# HP85disk_03.net
KiCad netlist of a schematic drawn in EAGLE
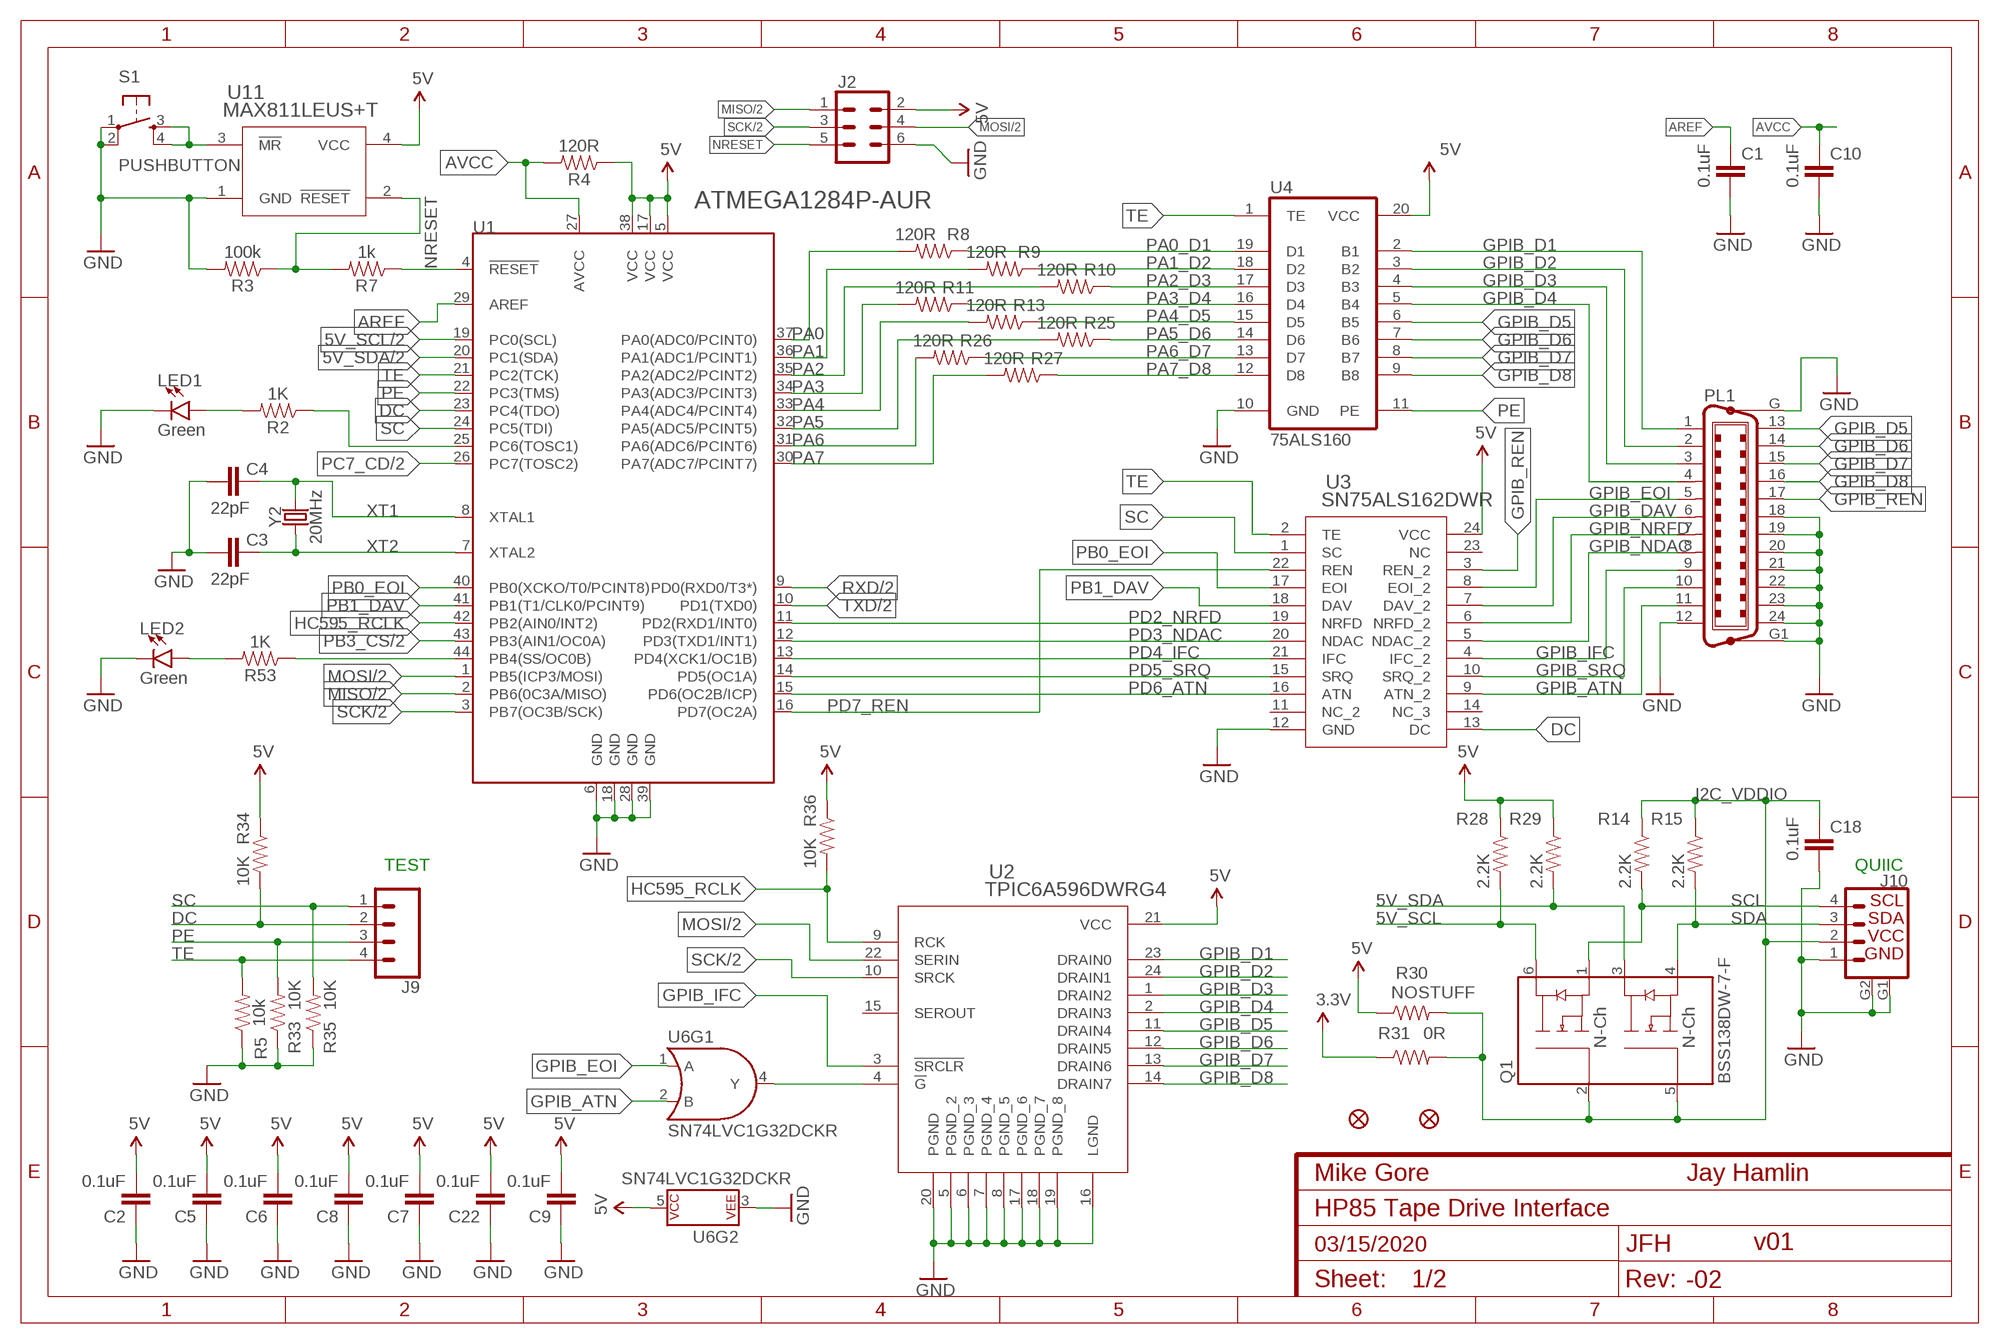
[diagram p0: schematic, sheet 1]
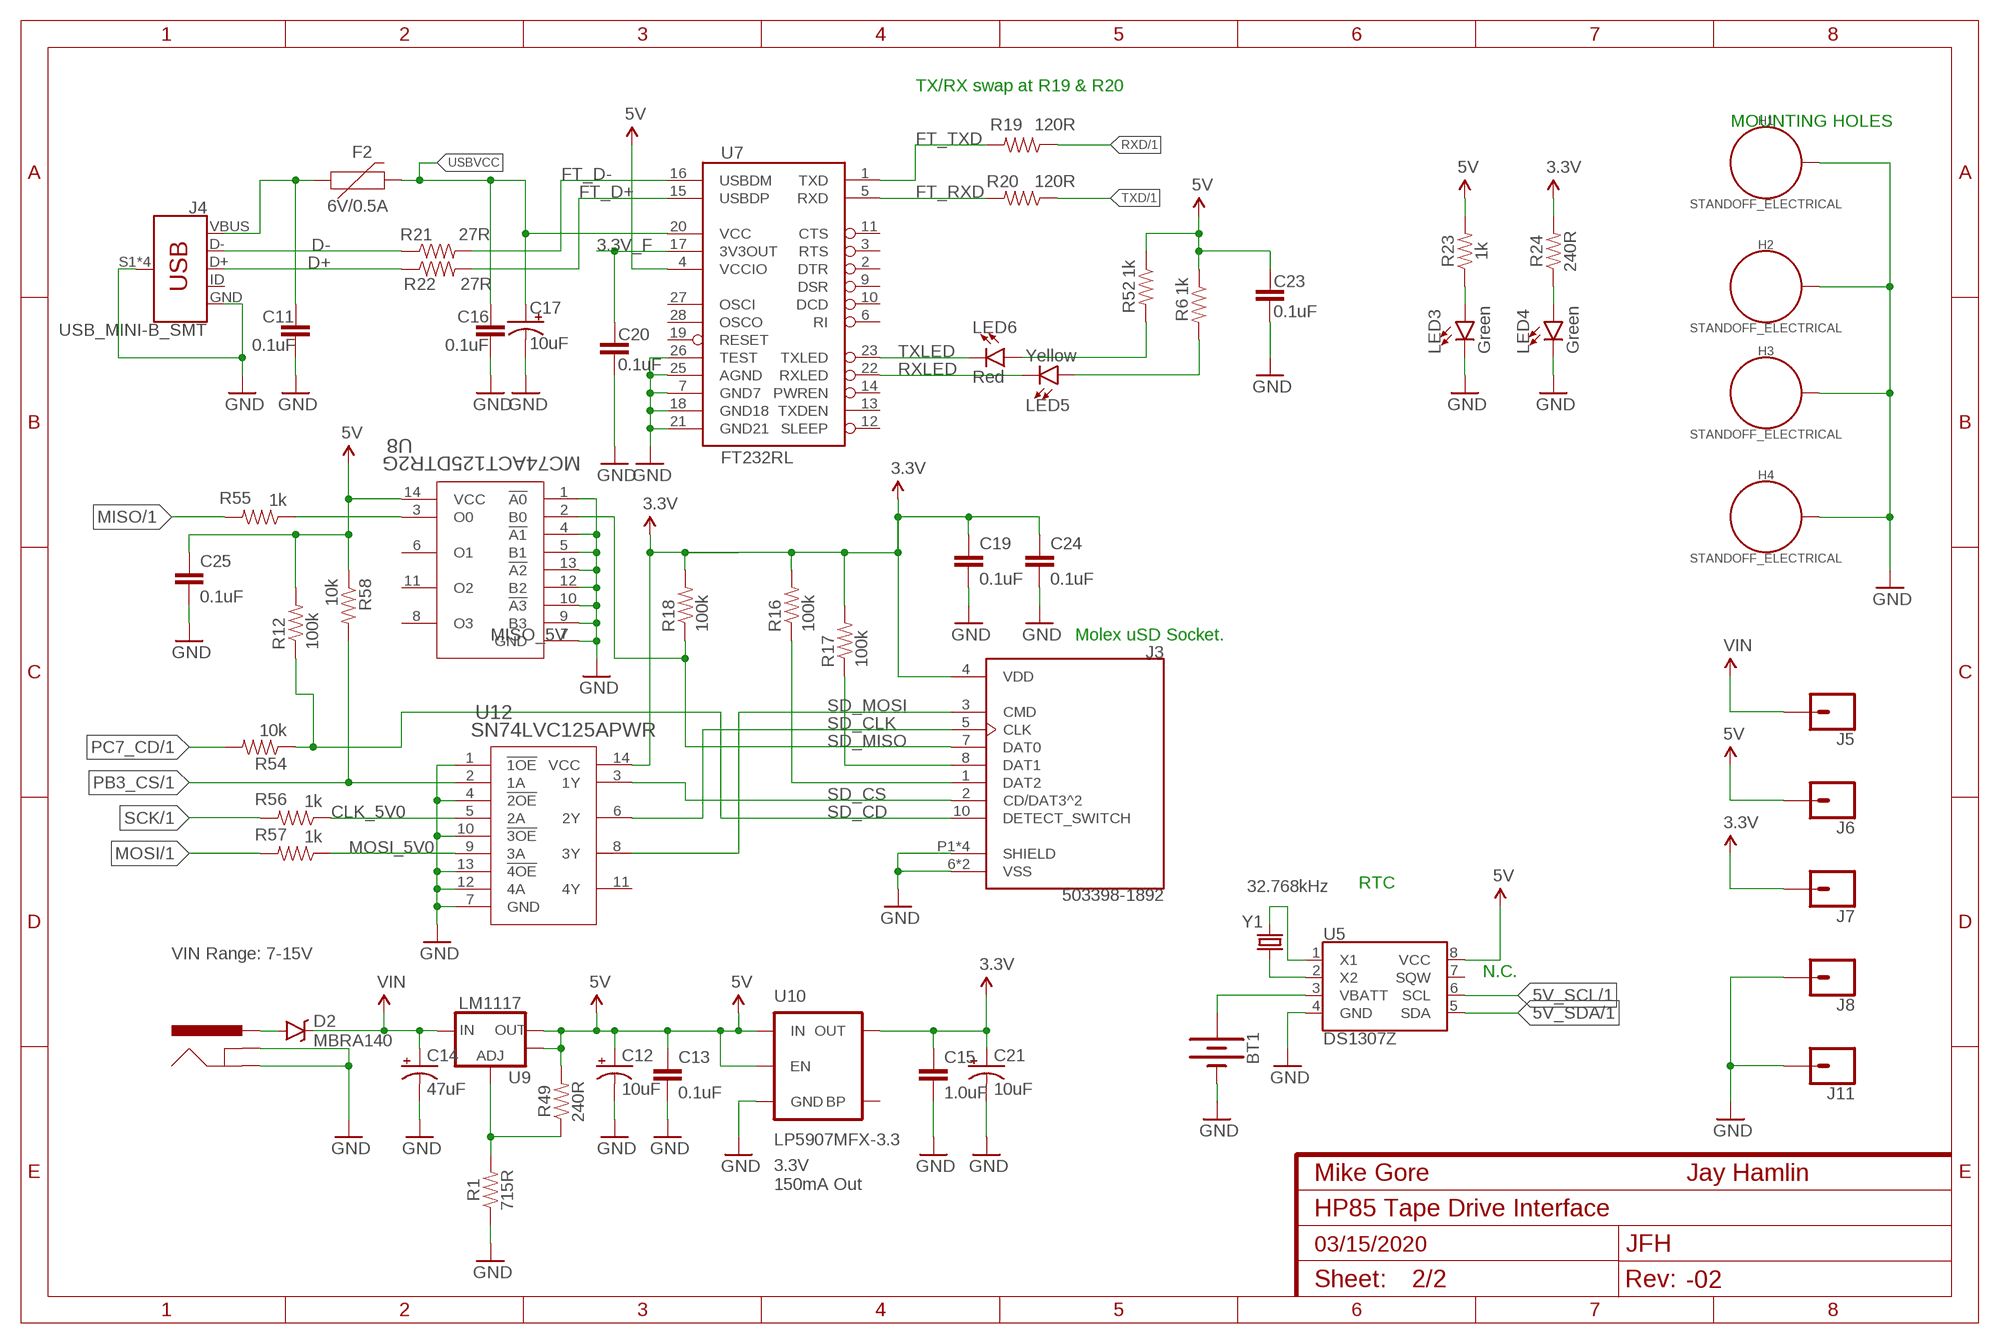
[diagram p1: schematic, sheet 2]

(export (version "E")
  (design (tool "Eeschema 10.0.6"))
  (components
    (comp (ref "C1")
      (value "0.1uF")
      (footprint "eagle-import:0603")
      (libsource (lib "eagle-import") (part "0.1UF-0603-25V-(+80/-20%)"))
    )
    (comp (ref "C2")
      (value "0.1uF")
      (footprint "eagle-import:0603")
      (fields (field (name "SPICEPREFIX") "C"))
      (libsource (lib "eagle-import") (part "0.1UF-0603-25V-(+80/-20%)"))
    )
    (comp (ref "C3")
      (value "22pF")
      (footprint "eagle-import:0603")
      (libsource (lib "eagle-import") (part "0.1UF-0603-25V-(+80/-20%)"))
    )
    (comp (ref "C4")
      (value "22pF")
      (footprint "eagle-import:0603")
      (libsource (lib "eagle-import") (part "0.1UF-0603-25V-(+80/-20%)"))
    )
    (comp (ref "C5")
      (value "0.1uF")
      (footprint "eagle-import:0603")
      (fields (field (name "SPICEPREFIX") "C"))
      (libsource (lib "eagle-import") (part "0.1UF-0603-25V-(+80/-20%)"))
    )
    (comp (ref "C6")
      (value "0.1uF")
      (footprint "eagle-import:0603")
      (fields (field (name "SPICEPREFIX") "C"))
      (libsource (lib "eagle-import") (part "0.1UF-0603-25V-(+80/-20%)"))
    )
    (comp (ref "C7")
      (value "0.1uF")
      (footprint "eagle-import:0603")
      (fields (field (name "SPICEPREFIX") "C"))
      (libsource (lib "eagle-import") (part "0.1UF-0603-25V-(+80/-20%)"))
    )
    (comp (ref "C8")
      (value "0.1uF")
      (footprint "eagle-import:0603")
      (fields (field (name "SPICEPREFIX") "C"))
      (libsource (lib "eagle-import") (part "0.1UF-0603-25V-(+80/-20%)"))
    )
    (comp (ref "C9")
      (value "0.1uF")
      (footprint "eagle-import:0603")
      (libsource (lib "eagle-import") (part "0.1UF-0603-25V-(+80/-20%)"))
    )
    (comp (ref "C10")
      (value "0.1uF")
      (footprint "eagle-import:0603")
      (libsource (lib "eagle-import") (part "0.1UF-0603-25V-(+80/-20%)"))
    )
    (comp (ref "C18")
      (value "0.1uF")
      (footprint "eagle-import:0603")
      (libsource (lib "eagle-import") (part "0.1UF-0603-25V-(+80/-20%)"))
    )
    (comp (ref "C22")
      (value "0.1uF")
      (footprint "eagle-import:0603")
      (libsource (lib "eagle-import") (part "0.1UF-0603-25V-(+80/-20%)"))
    )
    (comp (ref "J2")
      (value "CONN_03X2_BIGPADSFEMALE_SMD")
      (footprint "eagle-import:2X3_SMD")
      (libsource (lib "eagle-import") (part "CONN_03X2_BIGPADSFEMALE_SMD"))
    )
    (comp (ref "J9")
      (value "CONN_041.27MM")
      (footprint "eagle-import:1X04_1.27MM")
      (libsource (lib "eagle-import") (part "CONN_041.27MM"))
    )
    (comp (ref "J10")
      (value "QWIIC_CONNECTORJS-1MM")
      (footprint "eagle-import:QUIIC_1X04_1MM_RA")
      (libsource (lib "eagle-import") (part "QWIIC_CONNECTORJS-1MM"))
    )
    (comp (ref "JP8")
      (value "FIDUCIAL1X2")
      (footprint "eagle-import:FIDUCIAL-1X2")
      (libsource (lib "eagle-import") (part "FIDUCIAL1X2"))
    )
    (comp (ref "JP9")
      (value "FIDUCIAL1X2")
      (footprint "eagle-import:FIDUCIAL-1X2")
      (libsource (lib "eagle-import") (part "FIDUCIAL1X2"))
    )
    (comp (ref "LED1")
      (value "Green")
      (footprint "eagle-import:LED-1206")
      (libsource (lib "eagle-import") (part "LED1206"))
    )
    (comp (ref "LED2")
      (value "Green")
      (footprint "eagle-import:LED-1206")
      (libsource (lib "eagle-import") (part "LED1206"))
    )
    (comp (ref "PL1")
      (value "C24HP")
      (footprint "eagle-import:24HP")
      (libsource (lib "eagle-import") (part "C24HP"))
    )
    (comp (ref "Q1")
      (value "BSS138DW-7-F")
      (footprint "eagle-import:SOT-363")
      (libsource (lib "eagle-import") (part "BSS138DW-7-F"))
    )
    (comp (ref "R2")
      (value "1K")
      (footprint "eagle-import:0603")
      (libsource (lib "eagle-import") (part "4.7KOHM-0603-1/10W-1%"))
    )
    (comp (ref "R3")
      (value "100k")
      (footprint "eagle-import:0603")
      (libsource (lib "eagle-import") (part "10KOHM-0603-1/10W-1%"))
    )
    (comp (ref "R4")
      (value "120R")
      (footprint "eagle-import:0603")
      (libsource (lib "eagle-import") (part "10KOHM-0603-1/10W-1%"))
    )
    (comp (ref "R5")
      (value "10k")
      (footprint "eagle-import:0603")
      (libsource (lib "eagle-import") (part "10KOHM-0603-1/10W-1%"))
    )
    (comp (ref "R7")
      (value "1k")
      (footprint "eagle-import:0603")
      (libsource (lib "eagle-import") (part "10KOHM-0603-1/10W-1%"))
    )
    (comp (ref "R8")
      (value "120R")
      (footprint "eagle-import:0603")
      (libsource (lib "eagle-import") (part "10KOHM-0603-1/10W-1%"))
    )
    (comp (ref "R9")
      (value "120R")
      (footprint "eagle-import:0603")
      (libsource (lib "eagle-import") (part "10KOHM-0603-1/10W-1%"))
    )
    (comp (ref "R10")
      (value "120R")
      (footprint "eagle-import:0603")
      (libsource (lib "eagle-import") (part "10KOHM-0603-1/10W-1%"))
    )
    (comp (ref "R11")
      (value "120R")
      (footprint "eagle-import:0603")
      (libsource (lib "eagle-import") (part "10KOHM-0603-1/10W-1%"))
    )
    (comp (ref "R13")
      (value "120R")
      (footprint "eagle-import:0603")
      (libsource (lib "eagle-import") (part "10KOHM-0603-1/10W-1%"))
    )
    (comp (ref "R14")
      (value "2.2K")
      (footprint "eagle-import:0603")
      (libsource (lib "eagle-import") (part "10KOHM-0603-1/10W-1%"))
    )
    (comp (ref "R15")
      (value "2.2K")
      (footprint "eagle-import:0603")
      (libsource (lib "eagle-import") (part "10KOHM-0603-1/10W-1%"))
    )
    (comp (ref "R25")
      (value "120R")
      (footprint "eagle-import:0603")
      (libsource (lib "eagle-import") (part "10KOHM-0603-1/10W-1%"))
    )
    (comp (ref "R26")
      (value "120R")
      (footprint "eagle-import:0603")
      (libsource (lib "eagle-import") (part "10KOHM-0603-1/10W-1%"))
    )
    (comp (ref "R27")
      (value "120R")
      (footprint "eagle-import:0603")
      (libsource (lib "eagle-import") (part "10KOHM-0603-1/10W-1%"))
    )
    (comp (ref "R28")
      (value "2.2K")
      (footprint "eagle-import:0603")
      (libsource (lib "eagle-import") (part "10KOHM-0603-1/10W-1%"))
    )
    (comp (ref "R29")
      (value "2.2K")
      (footprint "eagle-import:0603")
      (libsource (lib "eagle-import") (part "10KOHM-0603-1/10W-1%"))
    )
    (comp (ref "R30")
      (value "NOSTUFF")
      (footprint "eagle-import:0603")
      (libsource (lib "eagle-import") (part "10KOHM-0603-1/10W-1%"))
    )
    (comp (ref "R31")
      (value "0R")
      (footprint "eagle-import:0603")
      (libsource (lib "eagle-import") (part "10KOHM-0603-1/10W-1%"))
    )
    (comp (ref "R33")
      (value "10K")
      (footprint "eagle-import:0603")
      (libsource (lib "eagle-import") (part "10KOHM-0603-1/10W-1%"))
    )
    (comp (ref "R34")
      (value "10K")
      (footprint "eagle-import:0603")
      (libsource (lib "eagle-import") (part "10KOHM-0603-1/10W-1%"))
    )
    (comp (ref "R35")
      (value "10K")
      (footprint "eagle-import:0603")
      (libsource (lib "eagle-import") (part "10KOHM-0603-1/10W-1%"))
    )
    (comp (ref "R36")
      (value "10K")
      (footprint "eagle-import:0603")
      (libsource (lib "eagle-import") (part "10KOHM-0603-1/10W-1%"))
    )
    (comp (ref "R53")
      (value "1K")
      (footprint "eagle-import:0603")
      (libsource (lib "eagle-import") (part "4.7KOHM-0603-1/10W-1%"))
    )
    (comp (ref "S1")
      (value "PUSHBUTTON")
      (footprint "eagle-import:TACTILE-SWITCH-SMD")
      (libsource (lib "eagle-import") (part "SWITCH_SPST_4_PINSQUARE"))
    )
    (comp (ref "U1")
      (value "ATMEGA1284P-AUR")
      (footprint "eagle-import:TQFP44")
      (libsource (lib "eagle-import") (part "ATMEGA1284AUTQFP-44"))
    )
    (comp (ref "U2")
      (value "TPIC6A596DWRG4")
      (footprint "eagle-import:DW24")
      (fields (field (name "MANUFACTURER") "Texas Instruments"))
      (libsource (lib "eagle-import") (part "TPIC6A596DWRG4"))
    )
    (comp (ref "U3")
      (value "SN75ALS162DWR")
      (footprint "eagle-import:DW24")
      (fields (field (name "MANUFACTURER") "Texas Instruments"))
      (libsource (lib "eagle-import") (part "SN75ALS162DWR"))
    )
    (comp (ref "U4")
      (value "75ALS160")
      (footprint "eagle-import:SO20L")
      (libsource (lib "eagle-import") (part "75160SO"))
    )
    (comp (ref "U6")
      (value "SN74LVC1G32DCKR")
      (footprint "eagle-import:SOT23-5")
      (libsource (lib "eagle-import") (part "7432DBVLVC"))
    )
    (comp (ref "U11")
      (value "MAX811LEUS+T")
      (footprint "eagle-import:21-0052F")
      (fields
        (field (name "MANUFACTURER_PART_NUMBER") "MAX811TEUS+T")
        (field (name "COPYRIGHT") "Copyright (C) 2018 Accelerated Designs. All rights reserved")
      )
      (libsource (lib "eagle-import") (part "MAX811TEUS+T"))
    )
    (comp (ref "Y2")
      (value "20MHz")
      (footprint "eagle-import:CRYSTAL-SMD-5X3.2-4PAD")
      (libsource (lib "eagle-import") (part "CRYSTAL-16MHZSMD-5X3.2"))
    )
    (comp (ref "BT1")
      (value "BATTERY-12MM_PTH")
      (footprint "eagle-import:BATTCON_12MM_PTH")
      (libsource (lib "eagle-import") (part "BATTERY-12MM_PTH"))
    )
    (comp (ref "C11")
      (value "0.1uF")
      (footprint "eagle-import:0603")
      (libsource (lib "eagle-import") (part "0.1UF-0603-25V-(+80/-20%)"))
    )
    (comp (ref "C12")
      (value "10uF")
      (footprint "eagle-import:EIA3216")
      (libsource (lib "eagle-import") (part "10UF-POLAR-EIA3216-16V-10%(TANT)"))
    )
    (comp (ref "C13")
      (value "0.1uF")
      (footprint "eagle-import:0603")
      (libsource (lib "eagle-import") (part "0.1UF-0603-25V-(+80/-20%)"))
    )
    (comp (ref "C14")
      (value "47uF")
      (footprint "eagle-import:PANASONIC_D")
      (libsource (lib "eagle-import") (part "47UF-POLAR-PANASONIC_D-35V-20%"))
    )
    (comp (ref "C15")
      (value "1.0uF")
      (footprint "eagle-import:0603")
      (libsource (lib "eagle-import") (part "1.0UF-0603-16V-10%"))
    )
    (comp (ref "C16")
      (value "0.1uF")
      (footprint "eagle-import:0603")
      (libsource (lib "eagle-import") (part "0.1UF-0603-25V-(+80/-20%)"))
    )
    (comp (ref "C17")
      (value "10uF")
      (footprint "eagle-import:EIA3216")
      (libsource (lib "eagle-import") (part "10UF-POLAR-EIA3216-16V-10%(TANT)"))
    )
    (comp (ref "C19")
      (value "0.1uF")
      (footprint "eagle-import:0603")
      (libsource (lib "eagle-import") (part "0.1UF-0603-25V-(+80/-20%)"))
    )
    (comp (ref "C20")
      (value "0.1uF")
      (footprint "eagle-import:0603")
      (libsource (lib "eagle-import") (part "0.1UF-0603-25V-(+80/-20%)"))
    )
    (comp (ref "C21")
      (value "10uF")
      (footprint "eagle-import:EIA3216")
      (libsource (lib "eagle-import") (part "10UF-POLAR-EIA3216-16V-10%(TANT)"))
    )
    (comp (ref "C23")
      (value "0.1uF")
      (footprint "eagle-import:0603")
      (libsource (lib "eagle-import") (part "0.1UF-0603-25V-(+80/-20%)"))
    )
    (comp (ref "C24")
      (value "0.1uF")
      (footprint "eagle-import:0603")
      (libsource (lib "eagle-import") (part "0.1UF-0603-25V-(+80/-20%)"))
    )
    (comp (ref "C25")
      (value "0.1uF")
      (footprint "eagle-import:0603")
      (libsource (lib "eagle-import") (part "0.1UF-0603-25V-(+80/-20%)"))
    )
    (comp (ref "D2")
      (value "MBRA140")
      (footprint "eagle-import:SMA-DIODE")
      (libsource (lib "eagle-import") (part "MBRA140"))
    )
    (comp (ref "F2")
      (value "6V/0.5A")
      (footprint "eagle-import:1206")
      (libsource (lib "eagle-import") (part "PTC-HALF_AMP"))
    )
    (comp (ref "H1")
      (value "STANDOFF_ELECTRICAL")
      (footprint "eagle-import:STANDOFF-ELECTRICAL")
      (libsource (lib "eagle-import") (part "STANDOFF_ELECTRICAL"))
    )
    (comp (ref "H2")
      (value "STANDOFF_ELECTRICAL")
      (footprint "eagle-import:STANDOFF-ELECTRICAL")
      (libsource (lib "eagle-import") (part "STANDOFF_ELECTRICAL"))
    )
    (comp (ref "H3")
      (value "STANDOFF_ELECTRICAL")
      (footprint "eagle-import:STANDOFF-ELECTRICAL")
      (libsource (lib "eagle-import") (part "STANDOFF_ELECTRICAL"))
    )
    (comp (ref "H4")
      (value "STANDOFF_ELECTRICAL")
      (footprint "eagle-import:STANDOFF-ELECTRICAL")
      (libsource (lib "eagle-import") (part "STANDOFF_ELECTRICAL"))
    )
    (comp (ref "J1")
      (value "POWER_JACKSUPER_BOMB_DIGITY")
      (footprint "eagle-import:POWER_JACK_SMD_OVERPASTE_SUPER_BOMB_DIGITY")
      (libsource (lib "eagle-import") (part "POWER_JACKSUPER_BOMB_DIGITY"))
    )
    (comp (ref "J3")
      (value "503398-1892")
      (footprint "eagle-import:MOLEX_503398-1892")
      (fields
        (field (name "DIGI-KEY_PART_NUMBER") "WM11190CT-ND")
        (field (name "MF") "Molex")
        (field (name "MP") "5033981892")
      )
      (libsource (lib "eagle-import") (part "503398-1892"))
    )
    (comp (ref "J4")
      (value "USB_MINI-B_SMT")
      (footprint "eagle-import:USB-MINIB")
      (libsource (lib "eagle-import") (part "USB_MINI-B_SMT"))
    )
    (comp (ref "J5")
      (value "CONN_01")
      (footprint "eagle-import:1X01")
      (libsource (lib "eagle-import") (part "CONN_01"))
    )
    (comp (ref "J6")
      (value "CONN_01")
      (footprint "eagle-import:1X01")
      (libsource (lib "eagle-import") (part "CONN_01"))
    )
    (comp (ref "J7")
      (value "CONN_01")
      (footprint "eagle-import:1X01")
      (libsource (lib "eagle-import") (part "CONN_01"))
    )
    (comp (ref "J8")
      (value "CONN_01")
      (footprint "eagle-import:1X01")
      (libsource (lib "eagle-import") (part "CONN_01"))
    )
    (comp (ref "J11")
      (value "CONN_01")
      (footprint "eagle-import:1X01")
      (libsource (lib "eagle-import") (part "CONN_01"))
    )
    (comp (ref "LED3")
      (value "Green")
      (footprint "eagle-import:LED-1206")
      (libsource (lib "eagle-import") (part "LED1206"))
    )
    (comp (ref "LED4")
      (value "Green")
      (footprint "eagle-import:LED-1206")
      (libsource (lib "eagle-import") (part "LED1206"))
    )
    (comp (ref "LED5")
      (value "Yellow")
      (footprint "eagle-import:LED-1206")
      (libsource (lib "eagle-import") (part "LED1206"))
    )
    (comp (ref "LED6")
      (value "Red")
      (footprint "eagle-import:LED-1206")
      (libsource (lib "eagle-import") (part "LED1206"))
    )
    (comp (ref "R1")
      (value "715R")
      (footprint "eagle-import:0603")
      (libsource (lib "eagle-import") (part "715OHM-0603-1/10W-1%"))
    )
    (comp (ref "R6")
      (value "1k")
      (footprint "eagle-import:0603")
      (libsource (lib "eagle-import") (part "1KOHM-0603-1/10W-1%"))
    )
    (comp (ref "R12")
      (value "100k")
      (footprint "eagle-import:0603-RES")
      (libsource (lib "eagle-import") (part "100KOHM-1/10W-1%(0603)"))
    )
    (comp (ref "R16")
      (value "100k")
      (footprint "eagle-import:0603-RES")
      (libsource (lib "eagle-import") (part "100KOHM-1/10W-1%(0603)"))
    )
    (comp (ref "R17")
      (value "100k")
      (footprint "eagle-import:0603-RES")
      (libsource (lib "eagle-import") (part "100KOHM-1/10W-1%(0603)"))
    )
    (comp (ref "R18")
      (value "100k")
      (footprint "eagle-import:0603-RES")
      (libsource (lib "eagle-import") (part "100KOHM-1/10W-1%(0603)"))
    )
    (comp (ref "R19")
      (value "120R")
      (footprint "eagle-import:0603")
      (libsource (lib "eagle-import") (part "1KOHM-0603-1/10W-1%"))
    )
    (comp (ref "R20")
      (value "120R")
      (footprint "eagle-import:0603")
      (libsource (lib "eagle-import") (part "1KOHM-0603-1/10W-1%"))
    )
    (comp (ref "R21")
      (value "27R")
      (footprint "eagle-import:0603")
      (libsource (lib "eagle-import") (part "27OHM-0603-1/10W-1%"))
    )
    (comp (ref "R22")
      (value "27R")
      (footprint "eagle-import:0603")
      (libsource (lib "eagle-import") (part "27OHM-0603-1/10W-1%"))
    )
    (comp (ref "R23")
      (value "1k")
      (footprint "eagle-import:0603")
      (libsource (lib "eagle-import") (part "4.7KOHM-0603-1/10W-1%"))
    )
    (comp (ref "R24")
      (value "240R")
      (footprint "eagle-import:0603")
      (libsource (lib "eagle-import") (part "4.7KOHM-0603-1/10W-1%"))
    )
    (comp (ref "R49")
      (value "240R")
      (footprint "eagle-import:0603")
      (libsource (lib "eagle-import") (part "240OHM-0603-1/10W-1%"))
    )
    (comp (ref "R52")
      (value "1k")
      (footprint "eagle-import:0603")
      (libsource (lib "eagle-import") (part "1KOHM-0603-1/10W-1%"))
    )
    (comp (ref "R54")
      (value "10k")
      (footprint "eagle-import:0603-RES")
      (libsource (lib "eagle-import") (part "100KOHM-1/10W-1%(0603)"))
    )
    (comp (ref "R55")
      (value "1k")
      (footprint "eagle-import:0603-RES")
      (libsource (lib "eagle-import") (part "100KOHM-1/10W-1%(0603)"))
    )
    (comp (ref "R56")
      (value "1k")
      (footprint "eagle-import:0603-RES")
      (libsource (lib "eagle-import") (part "100KOHM-1/10W-1%(0603)"))
    )
    (comp (ref "R57")
      (value "1k")
      (footprint "eagle-import:0603-RES")
      (libsource (lib "eagle-import") (part "100KOHM-1/10W-1%(0603)"))
    )
    (comp (ref "R58")
      (value "10k")
      (footprint "eagle-import:0603-RES")
      (libsource (lib "eagle-import") (part "100KOHM-1/10W-1%(0603)"))
    )
    (comp (ref "U5")
      (value "DS1307Z")
      (footprint "eagle-import:SO08-0.15")
      (libsource (lib "eagle-import") (part "DS1307Z"))
    )
    (comp (ref "U7")
      (value "FT232RL")
      (footprint "eagle-import:SSOP28DB")
      (libsource (lib "eagle-import") (part "FT232RLSSOP"))
    )
    (comp (ref "U8")
      (value "MC74ACT125DTR2G")
      (footprint "eagle-import:TSSOP14_4P50X5P10")
      (fields (field (name "COPYRIGHT") "Copyright (C) 2016 Accelerated Designs. All rights reserved"))
      (libsource (lib "eagle-import") (part "MC74ACT125DTR2G"))
    )
    (comp (ref "U9")
      (value "LM1117")
      (footprint "eagle-import:SOT223-ALT1")
      (libsource (lib "eagle-import") (part "V_REG_LM1117ALT1"))
    )
    (comp (ref "U10")
      (value "LP5907MFX-3.3")
      (footprint "eagle-import:SOT23-5")
      (libsource (lib "eagle-import") (part "MIC52053.3V"))
    )
    (comp (ref "U12")
      (value "SN74LVC125APWR")
      (footprint "eagle-import:PW14")
      (fields (field (name "MANUFACTURER") "Texas Instruments"))
      (libsource (lib "eagle-import") (part "SN74LVC125APWR"))
    )
    (comp (ref "Y1")
      (value "32.768kHz")
      (footprint "eagle-import:CRYSTAL-SMD-2X6-CYL")
      (libsource (lib "eagle-import") (part "CRYSTAL-32.768KHZSMD-2X6"))
    )
  )
  (nets
    (net (code "1") (name "3.3V") (class "Default")
      (node (ref "C15") (pin "1") (pinfunction "1_1") (pintype "passive"))
      (node (ref "C19") (pin "1") (pinfunction "1_1") (pintype "passive"))
      (node (ref "C21") (pin "+") (pinfunction "+_+") (pintype "passive"))
      (node (ref "C24") (pin "1") (pinfunction "1_1") (pintype "passive"))
      (node (ref "J3") (pin "4") (pinfunction "VDD_4") (pintype "power_in"))
      (node (ref "J7") (pin "1") (pinfunction "1_1") (pintype "passive"))
      (node (ref "R16") (pin "2") (pinfunction "2_2") (pintype "passive"))
      (node (ref "R17") (pin "2") (pinfunction "2_2") (pintype "passive"))
      (node (ref "R18") (pin "2") (pinfunction "2_2") (pintype "passive"))
      (node (ref "R24") (pin "2") (pinfunction "2_2") (pintype "passive"))
      (node (ref "R31") (pin "1") (pinfunction "1_1") (pintype "passive"))
      (node (ref "U10") (pin "5") (pinfunction "OUT_5") (pintype "passive"))
      (node (ref "U12") (pin "14") (pinfunction "VCC_14") (pintype "power_in"))
    )
    (net (code "2") (name "3.3V_F") (class "Default")
      (node (ref "C20") (pin "1") (pinfunction "1_1") (pintype "passive"))
      (node (ref "U7") (pin "17") (pinfunction "3V3OUT_17") (pintype "output"))
    )
    (net (code "3") (name "5V") (class "Default")
      (node (ref "C12") (pin "+") (pinfunction "+_+") (pintype "passive"))
      (node (ref "C13") (pin "1") (pinfunction "1_1") (pintype "passive"))
      (node (ref "C2") (pin "2") (pinfunction "2_2") (pintype "passive"))
      (node (ref "C22") (pin "2") (pinfunction "2_2") (pintype "passive"))
      (node (ref "C23") (pin "1") (pinfunction "1_1") (pintype "passive"))
      (node (ref "C25") (pin "1") (pinfunction "1_1") (pintype "passive"))
      (node (ref "C5") (pin "2") (pinfunction "2_2") (pintype "passive"))
      (node (ref "C6") (pin "2") (pinfunction "2_2") (pintype "passive"))
      (node (ref "C7") (pin "2") (pinfunction "2_2") (pintype "passive"))
      (node (ref "C8") (pin "2") (pinfunction "2_2") (pintype "passive"))
      (node (ref "C9") (pin "2") (pinfunction "2_2") (pintype "passive"))
      (node (ref "J2") (pin "2") (pinfunction "2_2") (pintype "bidirectional"))
      (node (ref "J6") (pin "1") (pinfunction "1_1") (pintype "passive"))
      (node (ref "R12") (pin "2") (pinfunction "2_2") (pintype "passive"))
      (node (ref "R23") (pin "2") (pinfunction "2_2") (pintype "passive"))
      (node (ref "R28") (pin "1") (pinfunction "1_1") (pintype "passive"))
      (node (ref "R29") (pin "1") (pinfunction "1_1") (pintype "passive"))
      (node (ref "R30") (pin "1") (pinfunction "1_1") (pintype "passive"))
      (node (ref "R34") (pin "1") (pinfunction "1_1") (pintype "passive"))
      (node (ref "R36") (pin "1") (pinfunction "1_1") (pintype "passive"))
      (node (ref "R4") (pin "1") (pinfunction "1_1") (pintype "passive"))
      (node (ref "R49") (pin "2") (pinfunction "2_2") (pintype "passive"))
      (node (ref "R52") (pin "1") (pinfunction "1_1") (pintype "passive"))
      (node (ref "R58") (pin "1") (pinfunction "1_1") (pintype "passive"))
      (node (ref "R6") (pin "1") (pinfunction "1_1") (pintype "passive"))
      (node (ref "U1") (pin "17") (pinfunction "VCC_17") (pintype "bidirectional"))
      (node (ref "U1") (pin "38") (pinfunction "VCC_38") (pintype "bidirectional"))
      (node (ref "U1") (pin "5") (pinfunction "VCC_5") (pintype "bidirectional"))
      (node (ref "U10") (pin "1") (pinfunction "IN_1") (pintype "input"))
      (node (ref "U10") (pin "3") (pinfunction "EN_3") (pintype "input"))
      (node (ref "U11") (pin "4") (pinfunction "VCC_4") (pintype "power_in"))
      (node (ref "U2") (pin "21") (pinfunction "VCC_21") (pintype "power_in"))
      (node (ref "U3") (pin "24") (pinfunction "VCC_24") (pintype "power_in"))
      (node (ref "U4") (pin "20") (pinfunction "VCC_20") (pintype "bidirectional"))
      (node (ref "U5") (pin "8") (pinfunction "VCC_8") (pintype "bidirectional"))
      (node (ref "U6") (pin "5") (pinfunction "P$V+_5") (pintype "bidirectional"))
      (node (ref "U7") (pin "4") (pinfunction "VCCIO_4") (pintype "power_in"))
      (node (ref "U8") (pin "14") (pinfunction "VCC_14") (pintype "power_in"))
      (node (ref "U9") (pin "2") (pinfunction "OUT_2") (pintype "output"))
      (node (ref "U9") (pin "4") (pinfunction "OUT_4") (pintype "output"))
    )
    (net (code "4") (name "5V_SCL") (class "Default")
      (node (ref "Q1") (pin "6") (pinfunction "D1_6") (pintype "bidirectional"))
      (node (ref "R28") (pin "2") (pinfunction "2_2") (pintype "passive"))
      (node (ref "U1") (pin "19") (pinfunction "PC0(SCL)_19") (pintype "bidirectional"))
      (node (ref "U5") (pin "6") (pinfunction "SCL_6") (pintype "bidirectional"))
    )
    (net (code "5") (name "5V_SDA") (class "Default")
      (node (ref "Q1") (pin "3") (pinfunction "D2_3") (pintype "bidirectional"))
      (node (ref "R29") (pin "2") (pinfunction "2_2") (pintype "passive"))
      (node (ref "U1") (pin "20") (pinfunction "PC1(SDA)_20") (pintype "bidirectional"))
      (node (ref "U5") (pin "5") (pinfunction "SDA_5") (pintype "bidirectional"))
    )
    (net (code "6") (name "AREF") (class "Default")
      (node (ref "C1") (pin "1") (pinfunction "1_1") (pintype "passive"))
      (node (ref "U1") (pin "29") (pinfunction "AREF_29") (pintype "bidirectional"))
    )
    (net (code "7") (name "AVCC") (class "Default")
      (node (ref "C10") (pin "1") (pinfunction "1_1") (pintype "passive"))
      (node (ref "R4") (pin "2") (pinfunction "2_2") (pintype "passive"))
      (node (ref "U1") (pin "27") (pinfunction "AVCC_27") (pintype "bidirectional"))
    )
    (net (code "8") (name "CLK_5V0") (class "Default")
      (node (ref "R56") (pin "1") (pinfunction "1_1") (pintype "passive"))
      (node (ref "U12") (pin "5") (pinfunction "2A_5") (pintype "input"))
    )
    (net (code "9") (name "D+") (class "Default")
      (node (ref "J4") (pin "D+") (pinfunction "D+_D+") (pintype "bidirectional"))
      (node (ref "R22") (pin "1") (pinfunction "1_1") (pintype "passive"))
    )
    (net (code "10") (name "D-") (class "Default")
      (node (ref "J4") (pin "D-") (pinfunction "D-_D-") (pintype "bidirectional"))
      (node (ref "R21") (pin "1") (pinfunction "1_1") (pintype "passive"))
    )
    (net (code "11") (name "DC") (class "Default")
      (node (ref "J9") (pin "2") (pinfunction "2_2") (pintype "passive"))
      (node (ref "R34") (pin "2") (pinfunction "2_2") (pintype "passive"))
      (node (ref "U1") (pin "23") (pinfunction "PC4(TDO)_23") (pintype "bidirectional"))
      (node (ref "U3") (pin "13") (pinfunction "DC_13") (pintype "input"))
    )
    (net (code "12") (name "FT_D+") (class "Default")
      (node (ref "R22") (pin "2") (pinfunction "2_2") (pintype "passive"))
      (node (ref "U7") (pin "15") (pinfunction "USBDP_15") (pintype "bidirectional"))
    )
    (net (code "13") (name "FT_D-") (class "Default")
      (node (ref "R21") (pin "2") (pinfunction "2_2") (pintype "passive"))
      (node (ref "U7") (pin "16") (pinfunction "USBDM_16") (pintype "bidirectional"))
    )
    (net (code "14") (name "FT_RXD") (class "Default")
      (node (ref "R20") (pin "2") (pinfunction "2_2") (pintype "passive"))
      (node (ref "U7") (pin "5") (pinfunction "RXD_5") (pintype "input"))
    )
    (net (code "15") (name "FT_TXD") (class "Default")
      (node (ref "R19") (pin "2") (pinfunction "2_2") (pintype "passive"))
      (node (ref "U7") (pin "1") (pinfunction "TXD_1") (pintype "output"))
    )
    (net (code "16") (name "GND") (class "Default")
      (node (ref "BT1") (pin "GND") (pinfunction "-_GND") (pintype "power_in"))
      (node (ref "C1") (pin "2") (pinfunction "2_2") (pintype "passive"))
      (node (ref "C10") (pin "2") (pinfunction "2_2") (pintype "passive"))
      (node (ref "C11") (pin "2") (pinfunction "2_2") (pintype "passive"))
      (node (ref "C12") (pin "-") (pinfunction "-_-") (pintype "passive"))
      (node (ref "C13") (pin "2") (pinfunction "2_2") (pintype "passive"))
      (node (ref "C14") (pin "-") (pinfunction "-_-") (pintype "passive"))
      (node (ref "C15") (pin "2") (pinfunction "2_2") (pintype "passive"))
      (node (ref "C16") (pin "2") (pinfunction "2_2") (pintype "passive"))
      (node (ref "C17") (pin "-") (pinfunction "-_-") (pintype "passive"))
      (node (ref "C18") (pin "2") (pinfunction "2_2") (pintype "passive"))
      (node (ref "C19") (pin "2") (pinfunction "2_2") (pintype "passive"))
      (node (ref "C2") (pin "1") (pinfunction "1_1") (pintype "passive"))
      (node (ref "C20") (pin "2") (pinfunction "2_2") (pintype "passive"))
      (node (ref "C21") (pin "-") (pinfunction "-_-") (pintype "passive"))
      (node (ref "C22") (pin "1") (pinfunction "1_1") (pintype "passive"))
      (node (ref "C23") (pin "2") (pinfunction "2_2") (pintype "passive"))
      (node (ref "C24") (pin "2") (pinfunction "2_2") (pintype "passive"))
      (node (ref "C25") (pin "2") (pinfunction "2_2") (pintype "passive"))
      (node (ref "C3") (pin "1") (pinfunction "1_1") (pintype "passive"))
      (node (ref "C4") (pin "1") (pinfunction "1_1") (pintype "passive"))
      (node (ref "C5") (pin "1") (pinfunction "1_1") (pintype "passive"))
      (node (ref "C6") (pin "1") (pinfunction "1_1") (pintype "passive"))
      (node (ref "C7") (pin "1") (pinfunction "1_1") (pintype "passive"))
      (node (ref "C8") (pin "1") (pinfunction "1_1") (pintype "passive"))
      (node (ref "C9") (pin "1") (pinfunction "1_1") (pintype "passive"))
      (node (ref "H1") (pin "P1") (pinfunction "P$1_P1") (pintype "bidirectional"))
      (node (ref "H2") (pin "P1") (pinfunction "P$1_P1") (pintype "bidirectional"))
      (node (ref "H3") (pin "P1") (pinfunction "P$1_P1") (pintype "bidirectional"))
      (node (ref "H4") (pin "P1") (pinfunction "P$1_P1") (pintype "bidirectional"))
      (node (ref "J1") (pin "GND") (pinfunction "GNDBREAK_GND") (pintype "bidirectional"))
      (node (ref "J1") (pin "P$4") (pinfunction "GND_P$4") (pintype "bidirectional"))
      (node (ref "J10") (pin "1") (pinfunction "1_1") (pintype "power_in"))
      (node (ref "J10") (pin "G1") (pinfunction "G1_G1") (pintype "power_in"))
      (node (ref "J10") (pin "G2") (pinfunction "G2_G2") (pintype "power_in"))
      (node (ref "J11") (pin "1") (pinfunction "1_1") (pintype "passive"))
      (node (ref "J2") (pin "6") (pinfunction "6_6") (pintype "bidirectional"))
      (node (ref "J3") (pin "6") (pinfunction "VSS_6") (pintype "power_in"))
      (node (ref "J3") (pin "9") (pinfunction "VSS_9") (pintype "power_in"))
      (node (ref "J3") (pin "P1") (pinfunction "SHIELD_P1") (pintype "passive"))
      (node (ref "J3") (pin "P2") (pinfunction "SHIELD_P2") (pintype "passive"))
      (node (ref "J3") (pin "P3") (pinfunction "SHIELD_P3") (pintype "passive"))
      (node (ref "J3") (pin "P4") (pinfunction "SHIELD_P4") (pintype "passive"))
      (node (ref "J4") (pin "GND") (pinfunction "GND_GND") (pintype "power_in"))
      (node (ref "J4") (pin "S1") (pinfunction "SHIELD_S1") (pintype "bidirectional"))
      (node (ref "J4") (pin "S2") (pinfunction "SHIELD_S2") (pintype "bidirectional"))
      (node (ref "J4") (pin "S3") (pinfunction "SHIELD_S3") (pintype "bidirectional"))
      (node (ref "J4") (pin "S4") (pinfunction "SHIELD_S4") (pintype "bidirectional"))
      (node (ref "J8") (pin "1") (pinfunction "1_1") (pintype "passive"))
      (node (ref "LED1") (pin "C") (pinfunction "C_C") (pintype "passive"))
      (node (ref "LED2") (pin "C") (pinfunction "C_C") (pintype "passive"))
      (node (ref "LED3") (pin "C") (pinfunction "C_C") (pintype "passive"))
      (node (ref "LED4") (pin "C") (pinfunction "C_C") (pintype "passive"))
      (node (ref "PL1") (pin "12") (pinfunction "12_12") (pintype "passive"))
      (node (ref "PL1") (pin "18") (pinfunction "18_18") (pintype "passive"))
      (node (ref "PL1") (pin "19") (pinfunction "19_19") (pintype "passive"))
      (node (ref "PL1") (pin "20") (pinfunction "20_20") (pintype "passive"))
      (node (ref "PL1") (pin "21") (pinfunction "21_21") (pintype "passive"))
      (node (ref "PL1") (pin "22") (pinfunction "22_22") (pintype "passive"))
      (node (ref "PL1") (pin "23") (pinfunction "23_23") (pintype "passive"))
      (node (ref "PL1") (pin "24") (pinfunction "24_24") (pintype "passive"))
      (node (ref "PL1") (pin "G") (pinfunction "G_G") (pintype "passive"))
      (node (ref "PL1") (pin "G1") (pinfunction "G1_G1") (pintype "passive"))
      (node (ref "R1") (pin "1") (pinfunction "1_1") (pintype "passive"))
      (node (ref "R3") (pin "2") (pinfunction "2_2") (pintype "passive"))
      (node (ref "R33") (pin "1") (pinfunction "1_1") (pintype "passive"))
      (node (ref "R35") (pin "1") (pinfunction "1_1") (pintype "passive"))
      (node (ref "R5") (pin "1") (pinfunction "1_1") (pintype "passive"))
      (node (ref "S1") (pin "1") (pinfunction "1_1") (pintype "passive"))
      (node (ref "S1") (pin "2") (pinfunction "2_2") (pintype "passive"))
      (node (ref "U1") (pin "18") (pinfunction "GND_18") (pintype "bidirectional"))
      (node (ref "U1") (pin "28") (pinfunction "GND_28") (pintype "bidirectional"))
      (node (ref "U1") (pin "39") (pinfunction "GND_39") (pintype "bidirectional"))
      (node (ref "U1") (pin "6") (pinfunction "GND_6") (pintype "bidirectional"))
      (node (ref "U10") (pin "2") (pinfunction "GND_2") (pintype "input"))
      (node (ref "U11") (pin "1") (pinfunction "GND_1") (pintype "power_in"))
      (node (ref "U12") (pin "1") (pinfunction "~{1OE}_1") (pintype "input"))
      (node (ref "U12") (pin "10") (pinfunction "~{3OE}_10") (pintype "input"))
      (node (ref "U12") (pin "12") (pinfunction "4A_12") (pintype "input"))
      (node (ref "U12") (pin "13") (pinfunction "~{4OE}_13") (pintype "input"))
      (node (ref "U12") (pin "4") (pinfunction "~{2OE}_4") (pintype "input"))
      (node (ref "U12") (pin "7") (pinfunction "GND_7") (pintype "power_in"))
      (node (ref "U2") (pin "16") (pinfunction "LGND_16") (pintype "power_in"))
      (node (ref "U2") (pin "17") (pinfunction "PGND_6_17") (pintype "power_in"))
      (node (ref "U2") (pin "18") (pinfunction "PGND_7_18") (pintype "power_in"))
      (node (ref "U2") (pin "19") (pinfunction "PGND_8_19") (pintype "power_in"))
      (node (ref "U2") (pin "20") (pinfunction "PGND_20") (pintype "power_in"))
      (node (ref "U2") (pin "5") (pinfunction "PGND_2_5") (pintype "power_in"))
      (node (ref "U2") (pin "6") (pinfunction "PGND_3_6") (pintype "power_in"))
      (node (ref "U2") (pin "7") (pinfunction "PGND_4_7") (pintype "power_in"))
      (node (ref "U2") (pin "8") (pinfunction "PGND_5_8") (pintype "power_in"))
      (node (ref "U3") (pin "12") (pinfunction "GND_12") (pintype "power_in"))
      (node (ref "U4") (pin "10") (pinfunction "GND_10") (pintype "bidirectional"))
      (node (ref "U5") (pin "4") (pinfunction "GND_4") (pintype "bidirectional"))
      (node (ref "U6") (pin "3") (pinfunction "P$V-_3") (pintype "bidirectional"))
      (node (ref "U7") (pin "18") (pinfunction "GND18_18") (pintype "power_in"))
      (node (ref "U7") (pin "21") (pinfunction "GND21_21") (pintype "power_in"))
      (node (ref "U7") (pin "25") (pinfunction "AGND_25") (pintype "power_in"))
      (node (ref "U7") (pin "26") (pinfunction "TEST_26") (pintype "input"))
      (node (ref "U7") (pin "7") (pinfunction "GND7_7") (pintype "power_in"))
      (node (ref "U8") (pin "1") (pinfunction "~{A0}_1") (pintype "input"))
      (node (ref "U8") (pin "10") (pinfunction "~{A3}_10") (pintype "input"))
      (node (ref "U8") (pin "12") (pinfunction "B2_12") (pintype "input"))
      (node (ref "U8") (pin "13") (pinfunction "~{A2}_13") (pintype "input"))
      (node (ref "U8") (pin "4") (pinfunction "~{A1}_4") (pintype "input"))
      (node (ref "U8") (pin "5") (pinfunction "B1_5") (pintype "input"))
      (node (ref "U8") (pin "7") (pinfunction "GND_7") (pintype "power_in"))
      (node (ref "U8") (pin "9") (pinfunction "B3_9") (pintype "input"))
    )
    (net (code "17") (name "GPIB_ATN") (class "Default")
      (node (ref "PL1") (pin "11") (pinfunction "11_11") (pintype "passive"))
      (node (ref "U3") (pin "9") (pinfunction "ATN_2_9") (pintype "bidirectional"))
      (node (ref "U6") (pin "2") (pinfunction "B_2") (pintype "bidirectional"))
    )
    (net (code "18") (name "GPIB_D1") (class "Default")
      (node (ref "PL1") (pin "1") (pinfunction "1_1") (pintype "passive"))
      (node (ref "U2") (pin "23") (pinfunction "DRAIN0_23") (pintype "output"))
      (node (ref "U4") (pin "2") (pinfunction "B1_2") (pintype "bidirectional"))
    )
    (net (code "19") (name "GPIB_D2") (class "Default")
      (node (ref "PL1") (pin "2") (pinfunction "2_2") (pintype "passive"))
      (node (ref "U2") (pin "24") (pinfunction "DRAIN1_24") (pintype "output"))
      (node (ref "U4") (pin "3") (pinfunction "B2_3") (pintype "bidirectional"))
    )
    (net (code "20") (name "GPIB_D3") (class "Default")
      (node (ref "PL1") (pin "3") (pinfunction "3_3") (pintype "passive"))
      (node (ref "U2") (pin "1") (pinfunction "DRAIN2_1") (pintype "output"))
      (node (ref "U4") (pin "4") (pinfunction "B3_4") (pintype "bidirectional"))
    )
    (net (code "21") (name "GPIB_D4") (class "Default")
      (node (ref "PL1") (pin "4") (pinfunction "4_4") (pintype "passive"))
      (node (ref "U2") (pin "2") (pinfunction "DRAIN3_2") (pintype "output"))
      (node (ref "U4") (pin "5") (pinfunction "B4_5") (pintype "bidirectional"))
    )
    (net (code "22") (name "GPIB_D5") (class "Default")
      (node (ref "PL1") (pin "13") (pinfunction "13_13") (pintype "passive"))
      (node (ref "U2") (pin "11") (pinfunction "DRAIN4_11") (pintype "output"))
      (node (ref "U4") (pin "6") (pinfunction "B5_6") (pintype "bidirectional"))
    )
    (net (code "23") (name "GPIB_D6") (class "Default")
      (node (ref "PL1") (pin "14") (pinfunction "14_14") (pintype "passive"))
      (node (ref "U2") (pin "12") (pinfunction "DRAIN5_12") (pintype "output"))
      (node (ref "U4") (pin "7") (pinfunction "B6_7") (pintype "bidirectional"))
    )
    (net (code "24") (name "GPIB_D7") (class "Default")
      (node (ref "PL1") (pin "15") (pinfunction "15_15") (pintype "passive"))
      (node (ref "U2") (pin "13") (pinfunction "DRAIN6_13") (pintype "output"))
      (node (ref "U4") (pin "8") (pinfunction "B7_8") (pintype "bidirectional"))
    )
    (net (code "25") (name "GPIB_D8") (class "Default")
      (node (ref "PL1") (pin "16") (pinfunction "16_16") (pintype "passive"))
      (node (ref "U2") (pin "14") (pinfunction "DRAIN7_14") (pintype "output"))
      (node (ref "U4") (pin "9") (pinfunction "B8_9") (pintype "bidirectional"))
    )
    (net (code "26") (name "GPIB_DAV") (class "Default")
      (node (ref "PL1") (pin "6") (pinfunction "6_6") (pintype "passive"))
      (node (ref "U3") (pin "7") (pinfunction "DAV_2_7") (pintype "bidirectional"))
    )
    (net (code "27") (name "GPIB_EOI") (class "Default")
      (node (ref "PL1") (pin "5") (pinfunction "5_5") (pintype "passive"))
      (node (ref "U3") (pin "8") (pinfunction "EOI_2_8") (pintype "bidirectional"))
      (node (ref "U6") (pin "1") (pinfunction "A_1") (pintype "bidirectional"))
    )
    (net (code "28") (name "GPIB_IFC") (class "Default")
      (node (ref "PL1") (pin "9") (pinfunction "9_9") (pintype "passive"))
      (node (ref "U2") (pin "3") (pinfunction "~{SRCLR}_3") (pintype "input"))
      (node (ref "U3") (pin "4") (pinfunction "IFC_2_4") (pintype "bidirectional"))
    )
    (net (code "29") (name "GPIB_NDAC") (class "Default")
      (node (ref "PL1") (pin "8") (pinfunction "8_8") (pintype "passive"))
      (node (ref "U3") (pin "5") (pinfunction "NDAC_2_5") (pintype "bidirectional"))
    )
    (net (code "30") (name "GPIB_NRFD") (class "Default")
      (node (ref "PL1") (pin "7") (pinfunction "7_7") (pintype "passive"))
      (node (ref "U3") (pin "6") (pinfunction "NRFD_2_6") (pintype "bidirectional"))
    )
    (net (code "31") (name "GPIB_REN") (class "Default")
      (node (ref "PL1") (pin "17") (pinfunction "17_17") (pintype "passive"))
      (node (ref "U3") (pin "3") (pinfunction "REN_2_3") (pintype "bidirectional"))
    )
    (net (code "32") (name "GPIB_SRQ") (class "Default")
      (node (ref "PL1") (pin "10") (pinfunction "10_10") (pintype "passive"))
      (node (ref "U3") (pin "10") (pinfunction "SRQ_2_10") (pintype "bidirectional"))
    )
    (net (code "33") (name "HC595_RCLK") (class "Default")
      (node (ref "R36") (pin "2") (pinfunction "2_2") (pintype "passive"))
      (node (ref "U1") (pin "42") (pinfunction "PB2(AIN0/INT2)_42") (pintype "bidirectional"))
      (node (ref "U2") (pin "9") (pinfunction "RCK_9") (pintype "input"))
    )
    (net (code "34") (name "I2C_VDDIO") (class "Default")
      (node (ref "C18") (pin "1") (pinfunction "1_1") (pintype "passive"))
      (node (ref "J10") (pin "2") (pinfunction "2_2") (pintype "power_in"))
      (node (ref "Q1") (pin "2") (pinfunction "G1_2") (pintype "bidirectional"))
      (node (ref "Q1") (pin "5") (pinfunction "G2_5") (pintype "bidirectional"))
      (node (ref "R14") (pin "1") (pinfunction "1_1") (pintype "passive"))
      (node (ref "R15") (pin "1") (pinfunction "1_1") (pintype "passive"))
      (node (ref "R30") (pin "2") (pinfunction "2_2") (pintype "passive"))
      (node (ref "R31") (pin "2") (pinfunction "2_2") (pintype "passive"))
    )
    (net (code "35") (name "MISO") (class "Default")
      (node (ref "J2") (pin "1") (pinfunction "1_1") (pintype "bidirectional"))
      (node (ref "R55") (pin "2") (pinfunction "2_2") (pintype "passive"))
      (node (ref "U1") (pin "2") (pinfunction "PB6(0C3A/MISO)_2") (pintype "bidirectional"))
    )
    (net (code "36") (name "MISO_5V") (class "Default")
      (node (ref "R55") (pin "1") (pinfunction "1_1") (pintype "passive"))
      (node (ref "U8") (pin "3") (pinfunction "O0_3") (pintype "output"))
    )
    (net (code "37") (name "MOSI") (class "Default")
      (node (ref "J2") (pin "4") (pinfunction "4_4") (pintype "bidirectional"))
      (node (ref "R57") (pin "2") (pinfunction "2_2") (pintype "passive"))
      (node (ref "U1") (pin "1") (pinfunction "PB5(ICP3/MOSI)_1") (pintype "bidirectional"))
      (node (ref "U2") (pin "22") (pinfunction "SERIN_22") (pintype "input"))
    )
    (net (code "38") (name "MOSI_5V0") (class "Default")
      (node (ref "R57") (pin "1") (pinfunction "1_1") (pintype "passive"))
      (node (ref "U12") (pin "9") (pinfunction "3A_9") (pintype "input"))
    )
    (net (code "39") (name "NRESET") (class "Default")
      (node (ref "J2") (pin "5") (pinfunction "5_5") (pintype "bidirectional"))
      (node (ref "R7") (pin "1") (pinfunction "1_1") (pintype "passive"))
      (node (ref "U1") (pin "4") (pinfunction "~{RESET}_4") (pintype "bidirectional"))
    )
    (net (code "40") (name "Net-(BT1-+)") (class "Default")
      (node (ref "BT1") (pin "VCC@1") (pinfunction "+_VCC@1") (pintype "power_in"))
      (node (ref "U5") (pin "3") (pinfunction "VBATT_3") (pintype "bidirectional"))
    )
    (net (code "41") (name "Net-(C11-Pad1)") (class "Default")
      (node (ref "C11") (pin "1") (pinfunction "1_1") (pintype "passive"))
      (node (ref "F2") (pin "1") (pinfunction "1_1") (pintype "bidirectional"))
      (node (ref "J4") (pin "VBUS") (pinfunction "VBUS_VBUS") (pintype "power_in"))
    )
    (net (code "42") (name "Net-(J1-PWR)") (class "Default")
      (node (ref "D2") (pin "A") (pinfunction "A_A") (pintype "passive"))
      (node (ref "J1") (pin "VIN0") (pinfunction "PWR_VIN0") (pintype "bidirectional"))
    )
    (net (code "43") (name "Net-(J3-DAT1)") (class "Default")
      (node (ref "J3") (pin "8") (pinfunction "DAT1_8") (pintype "passive"))
      (node (ref "R17") (pin "1") (pinfunction "1_1") (pintype "passive"))
    )
    (net (code "44") (name "Net-(J3-DAT2)") (class "Default")
      (node (ref "J3") (pin "1") (pinfunction "DAT2_1") (pintype "passive"))
      (node (ref "R16") (pin "1") (pinfunction "1_1") (pintype "passive"))
    )
    (net (code "45") (name "Net-(LED1-PadA)") (class "Default")
      (node (ref "LED1") (pin "A") (pinfunction "A_A") (pintype "passive"))
      (node (ref "R2") (pin "2") (pinfunction "2_2") (pintype "passive"))
    )
    (net (code "46") (name "Net-(LED2-PadA)") (class "Default")
      (node (ref "LED2") (pin "A") (pinfunction "A_A") (pintype "passive"))
      (node (ref "R53") (pin "2") (pinfunction "2_2") (pintype "passive"))
    )
    (net (code "47") (name "Net-(LED3-PadA)") (class "Default")
      (node (ref "LED3") (pin "A") (pinfunction "A_A") (pintype "passive"))
      (node (ref "R23") (pin "1") (pinfunction "1_1") (pintype "passive"))
    )
    (net (code "48") (name "Net-(LED4-PadA)") (class "Default")
      (node (ref "LED4") (pin "A") (pinfunction "A_A") (pintype "passive"))
      (node (ref "R24") (pin "1") (pinfunction "1_1") (pintype "passive"))
    )
    (net (code "49") (name "Net-(LED5-PadA)") (class "Default")
      (node (ref "LED5") (pin "A") (pinfunction "A_A") (pintype "passive"))
      (node (ref "R6") (pin "2") (pinfunction "2_2") (pintype "passive"))
    )
    (net (code "50") (name "Net-(LED6-PadA)") (class "Default")
      (node (ref "LED6") (pin "A") (pinfunction "A_A") (pintype "passive"))
      (node (ref "R52") (pin "2") (pinfunction "2_2") (pintype "passive"))
    )
    (net (code "51") (name "Net-(U1-PB4(SS{slash}OC0B))") (class "Default")
      (node (ref "R53") (pin "1") (pinfunction "1_1") (pintype "passive"))
      (node (ref "U1") (pin "44") (pinfunction "PB4(SS/OC0B)_44") (pintype "bidirectional"))
    )
    (net (code "52") (name "Net-(U1-PC6(TOSC1))") (class "Default")
      (node (ref "R2") (pin "1") (pinfunction "1_1") (pintype "passive"))
      (node (ref "U1") (pin "25") (pinfunction "PC6(TOSC1)_25") (pintype "bidirectional"))
    )
    (net (code "53") (name "Net-(U2-~{G})") (class "Default")
      (node (ref "U2") (pin "4") (pinfunction "~{G}_4") (pintype "input"))
      (node (ref "U6") (pin "4") (pinfunction "Y_4") (pintype "bidirectional"))
    )
    (net (code "54") (name "Net-(U5-X1)") (class "Default")
      (node (ref "U5") (pin "1") (pinfunction "X1_1") (pintype "bidirectional"))
      (node (ref "Y1") (pin "X2") (pinfunction "2_X2") (pintype "passive"))
    )
    (net (code "55") (name "Net-(U5-X2)") (class "Default")
      (node (ref "U5") (pin "2") (pinfunction "X2_2") (pintype "bidirectional"))
      (node (ref "Y1") (pin "X1") (pinfunction "1_X1") (pintype "passive"))
    )
    (net (code "56") (name "Net-(U9-ADJ)") (class "Default")
      (node (ref "R1") (pin "2") (pinfunction "2_2") (pintype "passive"))
      (node (ref "R49") (pin "1") (pinfunction "1_1") (pintype "passive"))
      (node (ref "U9") (pin "1") (pinfunction "ADJ_1") (pintype "input"))
    )
    (net (code "57") (name "Net-(U11-~{MR})") (class "Default")
      (node (ref "S1") (pin "3") (pinfunction "3_3") (pintype "passive"))
      (node (ref "S1") (pin "4") (pinfunction "4_4") (pintype "passive"))
      (node (ref "U11") (pin "3") (pinfunction "~{MR}_3") (pintype "input"))
    )
    (net (code "58") (name "Net-(U11-~{RESET})") (class "Default")
      (node (ref "R3") (pin "1") (pinfunction "1_1") (pintype "passive"))
      (node (ref "R7") (pin "2") (pinfunction "2_2") (pintype "passive"))
      (node (ref "U11") (pin "2") (pinfunction "~{RESET}_2") (pintype "output"))
    )
    (net (code "59") (name "PA0") (class "Default")
      (node (ref "R8") (pin "2") (pinfunction "2_2") (pintype "passive"))
      (node (ref "U1") (pin "37") (pinfunction "PA0(ADC0/PCINT0)_37") (pintype "bidirectional"))
    )
    (net (code "60") (name "PA0_D1") (class "Default")
      (node (ref "R8") (pin "1") (pinfunction "1_1") (pintype "passive"))
      (node (ref "U4") (pin "19") (pinfunction "D1_19") (pintype "bidirectional"))
    )
    (net (code "61") (name "PA1") (class "Default")
      (node (ref "R9") (pin "2") (pinfunction "2_2") (pintype "passive"))
      (node (ref "U1") (pin "36") (pinfunction "PA1(ADC1/PCINT1)_36") (pintype "bidirectional"))
    )
    (net (code "62") (name "PA1_D2") (class "Default")
      (node (ref "R9") (pin "1") (pinfunction "1_1") (pintype "passive"))
      (node (ref "U4") (pin "18") (pinfunction "D2_18") (pintype "bidirectional"))
    )
    (net (code "63") (name "PA2") (class "Default")
      (node (ref "R10") (pin "2") (pinfunction "2_2") (pintype "passive"))
      (node (ref "U1") (pin "35") (pinfunction "PA2(ADC2/PCINT2)_35") (pintype "bidirectional"))
    )
    (net (code "64") (name "PA2_D3") (class "Default")
      (node (ref "R10") (pin "1") (pinfunction "1_1") (pintype "passive"))
      (node (ref "U4") (pin "17") (pinfunction "D3_17") (pintype "bidirectional"))
    )
    (net (code "65") (name "PA3") (class "Default")
      (node (ref "R11") (pin "2") (pinfunction "2_2") (pintype "passive"))
      (node (ref "U1") (pin "34") (pinfunction "PA3(ADC3/PCINT3)_34") (pintype "bidirectional"))
    )
    (net (code "66") (name "PA3_D4") (class "Default")
      (node (ref "R11") (pin "1") (pinfunction "1_1") (pintype "passive"))
      (node (ref "U4") (pin "16") (pinfunction "D4_16") (pintype "bidirectional"))
    )
    (net (code "67") (name "PA4") (class "Default")
      (node (ref "R13") (pin "2") (pinfunction "2_2") (pintype "passive"))
      (node (ref "U1") (pin "33") (pinfunction "PA4(ADC4/PCINT4)_33") (pintype "bidirectional"))
    )
    (net (code "68") (name "PA4_D5") (class "Default")
      (node (ref "R13") (pin "1") (pinfunction "1_1") (pintype "passive"))
      (node (ref "U4") (pin "15") (pinfunction "D5_15") (pintype "bidirectional"))
    )
    (net (code "69") (name "PA5") (class "Default")
      (node (ref "R25") (pin "2") (pinfunction "2_2") (pintype "passive"))
      (node (ref "U1") (pin "32") (pinfunction "PA5(ADC5/PCINT5)_32") (pintype "bidirectional"))
    )
    (net (code "70") (name "PA5_D6") (class "Default")
      (node (ref "R25") (pin "1") (pinfunction "1_1") (pintype "passive"))
      (node (ref "U4") (pin "14") (pinfunction "D6_14") (pintype "bidirectional"))
    )
    (net (code "71") (name "PA6") (class "Default")
      (node (ref "R26") (pin "2") (pinfunction "2_2") (pintype "passive"))
      (node (ref "U1") (pin "31") (pinfunction "PA6(ADC6/PCINT6)_31") (pintype "bidirectional"))
    )
    (net (code "72") (name "PA6_D7") (class "Default")
      (node (ref "R26") (pin "1") (pinfunction "1_1") (pintype "passive"))
      (node (ref "U4") (pin "13") (pinfunction "D7_13") (pintype "bidirectional"))
    )
    (net (code "73") (name "PA7") (class "Default")
      (node (ref "R27") (pin "2") (pinfunction "2_2") (pintype "passive"))
      (node (ref "U1") (pin "30") (pinfunction "PA7(ADC7/PCINT7)_30") (pintype "bidirectional"))
    )
    (net (code "74") (name "PA7_D8") (class "Default")
      (node (ref "R27") (pin "1") (pinfunction "1_1") (pintype "passive"))
      (node (ref "U4") (pin "12") (pinfunction "D8_12") (pintype "bidirectional"))
    )
    (net (code "75") (name "PB0_EOI") (class "Default")
      (node (ref "U1") (pin "40") (pinfunction "PB0(XCKO/T0/PCINT8)_40") (pintype "bidirectional"))
      (node (ref "U3") (pin "17") (pinfunction "EOI_17") (pintype "bidirectional"))
    )
    (net (code "76") (name "PB1_DAV") (class "Default")
      (node (ref "U1") (pin "41") (pinfunction "PB1(T1/CLK0/PCINT9)_41") (pintype "bidirectional"))
      (node (ref "U3") (pin "18") (pinfunction "DAV_18") (pintype "bidirectional"))
    )
    (net (code "77") (name "PB3_CS") (class "Default")
      (node (ref "R58") (pin "2") (pinfunction "2_2") (pintype "passive"))
      (node (ref "U1") (pin "43") (pinfunction "PB3(AIN1/OC0A)_43") (pintype "bidirectional"))
      (node (ref "U12") (pin "2") (pinfunction "1A_2") (pintype "input"))
    )
    (net (code "78") (name "PC7_CD") (class "Default")
      (node (ref "R54") (pin "2") (pinfunction "2_2") (pintype "passive"))
      (node (ref "U1") (pin "26") (pinfunction "PC7(TOSC2)_26") (pintype "bidirectional"))
    )
    (net (code "79") (name "PD2_NRFD") (class "Default")
      (node (ref "U1") (pin "11") (pinfunction "PD2(RXD1/INT0)_11") (pintype "bidirectional"))
      (node (ref "U3") (pin "19") (pinfunction "NRFD_19") (pintype "bidirectional"))
    )
    (net (code "80") (name "PD3_NDAC") (class "Default")
      (node (ref "U1") (pin "12") (pinfunction "PD3(TXD1/INT1)_12") (pintype "bidirectional"))
      (node (ref "U3") (pin "20") (pinfunction "NDAC_20") (pintype "bidirectional"))
    )
    (net (code "81") (name "PD4_IFC") (class "Default")
      (node (ref "U1") (pin "13") (pinfunction "PD4(XCK1/OC1B)_13") (pintype "bidirectional"))
      (node (ref "U3") (pin "21") (pinfunction "IFC_21") (pintype "bidirectional"))
    )
    (net (code "82") (name "PD5_SRQ") (class "Default")
      (node (ref "U1") (pin "14") (pinfunction "PD5(OC1A)_14") (pintype "bidirectional"))
      (node (ref "U3") (pin "15") (pinfunction "SRQ_15") (pintype "bidirectional"))
    )
    (net (code "83") (name "PD6_ATN") (class "Default")
      (node (ref "U1") (pin "15") (pinfunction "PD6(OC2B/ICP)_15") (pintype "bidirectional"))
      (node (ref "U3") (pin "16") (pinfunction "ATN_16") (pintype "bidirectional"))
    )
    (net (code "84") (name "PD7_REN") (class "Default")
      (node (ref "U1") (pin "16") (pinfunction "PD7(OC2A)_16") (pintype "bidirectional"))
      (node (ref "U3") (pin "22") (pinfunction "REN_22") (pintype "bidirectional"))
    )
    (net (code "85") (name "PE") (class "Default")
      (node (ref "J9") (pin "3") (pinfunction "3_3") (pintype "passive"))
      (node (ref "R33") (pin "2") (pinfunction "2_2") (pintype "passive"))
      (node (ref "U1") (pin "22") (pinfunction "PC3(TMS)_22") (pintype "bidirectional"))
      (node (ref "U4") (pin "11") (pinfunction "PE_11") (pintype "input"))
    )
    (net (code "86") (name "RXD") (class "Default")
      (node (ref "R19") (pin "1") (pinfunction "1_1") (pintype "passive"))
      (node (ref "U1") (pin "9") (pinfunction "PD0(RXD0/T3*)_9") (pintype "bidirectional"))
    )
    (net (code "87") (name "RXLED") (class "Default")
      (node (ref "LED5") (pin "C") (pinfunction "C_C") (pintype "passive"))
      (node (ref "U7") (pin "22") (pinfunction "RXLED_22") (pintype "input"))
    )
    (net (code "88") (name "SC") (class "Default")
      (node (ref "J9") (pin "1") (pinfunction "1_1") (pintype "passive"))
      (node (ref "R35") (pin "2") (pinfunction "2_2") (pintype "passive"))
      (node (ref "U1") (pin "24") (pinfunction "PC5(TDI)_24") (pintype "bidirectional"))
      (node (ref "U3") (pin "1") (pinfunction "SC_1") (pintype "input"))
    )
    (net (code "89") (name "SCK") (class "Default")
      (node (ref "J2") (pin "3") (pinfunction "3_3") (pintype "bidirectional"))
      (node (ref "R56") (pin "2") (pinfunction "2_2") (pintype "passive"))
      (node (ref "U1") (pin "3") (pinfunction "PB7(OC3B/SCK)_3") (pintype "bidirectional"))
      (node (ref "U2") (pin "10") (pinfunction "SRCK_10") (pintype "input"))
    )
    (net (code "90") (name "SCL") (class "Default")
      (node (ref "J10") (pin "4") (pinfunction "4_4") (pintype "passive"))
      (node (ref "Q1") (pin "1") (pinfunction "S1_1") (pintype "bidirectional"))
      (node (ref "R14") (pin "2") (pinfunction "2_2") (pintype "passive"))
    )
    (net (code "91") (name "SDA") (class "Default")
      (node (ref "J10") (pin "3") (pinfunction "3_3") (pintype "passive"))
      (node (ref "Q1") (pin "4") (pinfunction "S2_4") (pintype "bidirectional"))
      (node (ref "R15") (pin "2") (pinfunction "2_2") (pintype "passive"))
    )
    (net (code "92") (name "SD_CD") (class "Default")
      (node (ref "J3") (pin "10") (pinfunction "DETECT_SWITCH_10") (pintype "passive"))
      (node (ref "R12") (pin "1") (pinfunction "1_1") (pintype "passive"))
      (node (ref "R54") (pin "1") (pinfunction "1_1") (pintype "passive"))
    )
    (net (code "93") (name "SD_CLK") (class "Default")
      (node (ref "J3") (pin "5") (pinfunction "CLK_5") (pintype "passive"))
      (node (ref "U12") (pin "6") (pinfunction "2Y_6") (pintype "output"))
    )
    (net (code "94") (name "SD_CS") (class "Default")
      (node (ref "J3") (pin "2") (pinfunction "CD/DAT3^2_2") (pintype "passive"))
      (node (ref "U12") (pin "3") (pinfunction "1Y_3") (pintype "output"))
    )
    (net (code "95") (name "SD_MISO") (class "Default")
      (node (ref "J3") (pin "7") (pinfunction "DAT0_7") (pintype "passive"))
      (node (ref "R18") (pin "1") (pinfunction "1_1") (pintype "passive"))
      (node (ref "U8") (pin "2") (pinfunction "B0_2") (pintype "input"))
    )
    (net (code "96") (name "SD_MOSI") (class "Default")
      (node (ref "J3") (pin "3") (pinfunction "CMD_3") (pintype "passive"))
      (node (ref "U12") (pin "8") (pinfunction "3Y_8") (pintype "output"))
    )
    (net (code "97") (name "TE") (class "Default")
      (node (ref "J9") (pin "4") (pinfunction "4_4") (pintype "passive"))
      (node (ref "R5") (pin "2") (pinfunction "2_2") (pintype "passive"))
      (node (ref "U1") (pin "21") (pinfunction "PC2(TCK)_21") (pintype "bidirectional"))
      (node (ref "U3") (pin "2") (pinfunction "TE_2") (pintype "input"))
      (node (ref "U4") (pin "1") (pinfunction "TE_1") (pintype "input"))
    )
    (net (code "98") (name "TXD") (class "Default")
      (node (ref "R20") (pin "1") (pinfunction "1_1") (pintype "passive"))
      (node (ref "U1") (pin "10") (pinfunction "PD1(TXD0)_10") (pintype "bidirectional"))
    )
    (net (code "99") (name "TXLED") (class "Default")
      (node (ref "LED6") (pin "C") (pinfunction "C_C") (pintype "passive"))
      (node (ref "U7") (pin "23") (pinfunction "TXLED_23") (pintype "input"))
    )
    (net (code "100") (name "USBVCC") (class "Default")
      (node (ref "C16") (pin "1") (pinfunction "1_1") (pintype "passive"))
      (node (ref "C17") (pin "+") (pinfunction "+_+") (pintype "passive"))
      (node (ref "F2") (pin "2") (pinfunction "2_2") (pintype "bidirectional"))
      (node (ref "U7") (pin "20") (pinfunction "VCC_20") (pintype "power_in"))
    )
    (net (code "101") (name "VIN") (class "Default")
      (node (ref "C14") (pin "+") (pinfunction "+_+") (pintype "passive"))
      (node (ref "D2") (pin "C") (pinfunction "C_C") (pintype "passive"))
      (node (ref "J5") (pin "1") (pinfunction "1_1") (pintype "passive"))
      (node (ref "U9") (pin "3") (pinfunction "IN_3") (pintype "input"))
    )
    (net (code "102") (name "XT1") (class "Default")
      (node (ref "C4") (pin "2") (pinfunction "2_2") (pintype "passive"))
      (node (ref "U1") (pin "8") (pinfunction "XTAL1_8") (pintype "bidirectional"))
      (node (ref "Y2") (pin "3") (pinfunction "2_3") (pintype "passive"))
    )
    (net (code "103") (name "XT2") (class "Default")
      (node (ref "C3") (pin "2") (pinfunction "2_2") (pintype "passive"))
      (node (ref "U1") (pin "7") (pinfunction "XTAL2_7") (pintype "bidirectional"))
      (node (ref "Y2") (pin "1") (pinfunction "1_1") (pintype "passive"))
    )
    (net (code "104") (name "unconnected-(J4-PadID)") (class "Default")
      (node (ref "J4") (pin "ID") (pinfunction "ID_ID") (pintype "bidirectional"))
    )
    (net (code "105") (name "unconnected-(U2-SEROUT-Pad15)") (class "Default")
      (node (ref "U2") (pin "15") (pinfunction "SEROUT_15") (pintype "output"))
    )
    (net (code "106") (name "unconnected-(U3-NC-Pad23)") (class "Default")
      (node (ref "U3") (pin "23") (pinfunction "NC_23") (pintype "passive"))
    )
    (net (code "107") (name "unconnected-(U3-NC_2-Pad11)") (class "Default")
      (node (ref "U3") (pin "11") (pinfunction "NC_2_11") (pintype "passive"))
    )
    (net (code "108") (name "unconnected-(U3-NC_3-Pad14)") (class "Default")
      (node (ref "U3") (pin "14") (pinfunction "NC_3_14") (pintype "passive"))
    )
    (net (code "109") (name "unconnected-(U5-SQW-Pad7)") (class "Default")
      (node (ref "U5") (pin "7") (pinfunction "SQW_7") (pintype "bidirectional"))
    )
    (net (code "110") (name "unconnected-(U7-CTS-Pad11)") (class "Default")
      (node (ref "U7") (pin "11") (pinfunction "CTS_11") (pintype "input"))
    )
    (net (code "111") (name "unconnected-(U7-DCD-Pad10)") (class "Default")
      (node (ref "U7") (pin "10") (pinfunction "DCD_10") (pintype "input"))
    )
    (net (code "112") (name "unconnected-(U7-DSR-Pad9)") (class "Default")
      (node (ref "U7") (pin "9") (pinfunction "DSR_9") (pintype "input"))
    )
    (net (code "113") (name "unconnected-(U7-DTR-Pad2)") (class "Default")
      (node (ref "U7") (pin "2") (pinfunction "DTR_2") (pintype "output"))
    )
    (net (code "114") (name "unconnected-(U7-OSCI-Pad27)") (class "Default")
      (node (ref "U7") (pin "27") (pinfunction "OSCI_27") (pintype "input"))
    )
    (net (code "115") (name "unconnected-(U7-OSCO-Pad28)") (class "Default")
      (node (ref "U7") (pin "28") (pinfunction "OSCO_28") (pintype "output"))
    )
    (net (code "116") (name "unconnected-(U7-PWREN-Pad14)") (class "Default")
      (node (ref "U7") (pin "14") (pinfunction "PWREN_14") (pintype "input"))
    )
    (net (code "117") (name "unconnected-(U7-RESET-Pad19)") (class "Default")
      (node (ref "U7") (pin "19") (pinfunction "RESET_19") (pintype "input"))
    )
    (net (code "118") (name "unconnected-(U7-RI-Pad6)") (class "Default")
      (node (ref "U7") (pin "6") (pinfunction "RI_6") (pintype "input"))
    )
    (net (code "119") (name "unconnected-(U7-RTS-Pad3)") (class "Default")
      (node (ref "U7") (pin "3") (pinfunction "RTS_3") (pintype "output"))
    )
    (net (code "120") (name "unconnected-(U7-SLEEP-Pad12)") (class "Default")
      (node (ref "U7") (pin "12") (pinfunction "SLEEP_12") (pintype "input"))
    )
    (net (code "121") (name "unconnected-(U7-TXDEN-Pad13)") (class "Default")
      (node (ref "U7") (pin "13") (pinfunction "TXDEN_13") (pintype "input"))
    )
    (net (code "122") (name "unconnected-(U8-O1-Pad6)") (class "Default")
      (node (ref "U8") (pin "6") (pinfunction "O1_6") (pintype "output"))
    )
    (net (code "123") (name "unconnected-(U8-O2-Pad11)") (class "Default")
      (node (ref "U8") (pin "11") (pinfunction "O2_11") (pintype "output"))
    )
    (net (code "124") (name "unconnected-(U8-O3-Pad8)") (class "Default")
      (node (ref "U8") (pin "8") (pinfunction "O3_8") (pintype "output"))
    )
    (net (code "125") (name "unconnected-(U10-BP-Pad4)") (class "Default")
      (node (ref "U10") (pin "4") (pinfunction "BP_4") (pintype "input"))
    )
    (net (code "126") (name "unconnected-(U12-4Y-Pad11)") (class "Default")
      (node (ref "U12") (pin "11") (pinfunction "4Y_11") (pintype "output"))
    )
  )
)
